# mdriver_8231A.net
KiCad netlist of a schematic drawn in EAGLE
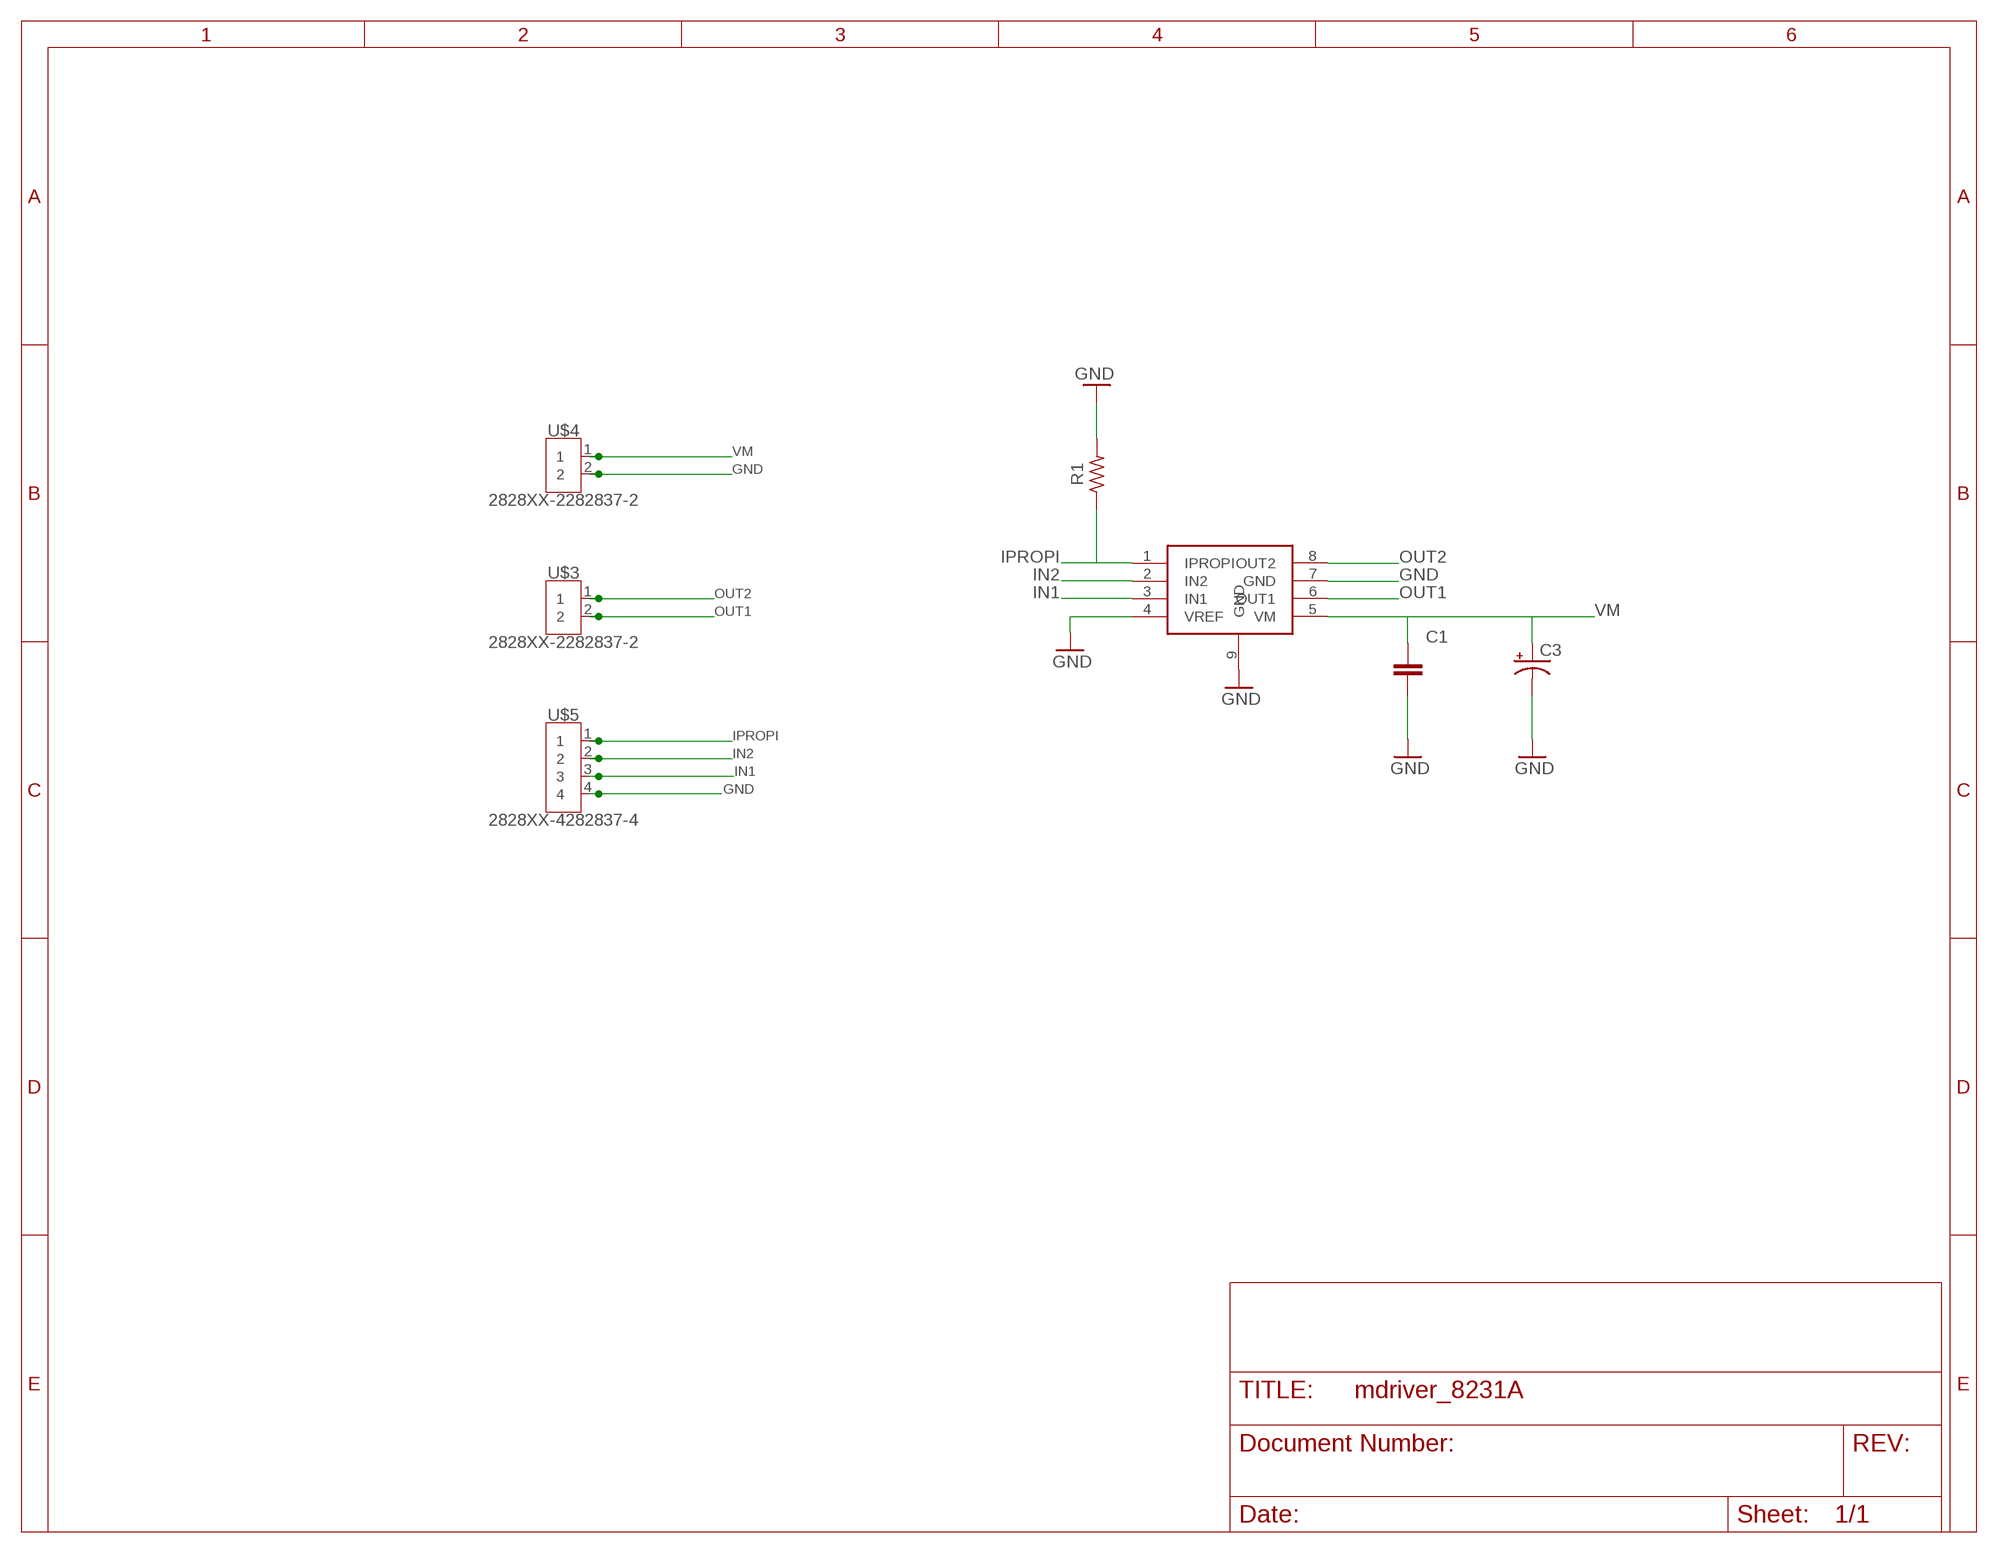
[diagram p0: schematic, sheet 1]

(export (version "E")
  (design (tool "Eeschema 10.0.6"))
  (components
    (comp (ref "C1")
      (value "C_CHIP-1206(3216-METRIC)")
      (footprint "eagle-import:CAPC3216X135")
      (libsource (lib "eagle-import") (part "CCHIP-1206(3216-METRIC)_"))
    )
    (comp (ref "C3")
      (value "C-POL-US_ECAP-10.5MM")
      (footprint "eagle-import:CAPAE1030X1050N")
      (libsource (lib "eagle-import") (part "C-POL-USECAP-10.5MM_"))
    )
    (comp (ref "R1")
      (value "R-US_CHIP-0603(1608-METRIC)")
      (footprint "eagle-import:RESC1608X60")
      (libsource (lib "eagle-import") (part "R-USCHIP-0603(1608-METRIC)_"))
    )
    (comp (ref "U$1")
      (value "DRV8231A")
      (footprint "eagle-import:SOIC127P580X170-9T271X340N")
      (libsource (lib "eagle-import") (part "DRV8231A"))
    )
    (comp (ref "U$3")
      (value "2828XX-2282837-2")
      (footprint "eagle-import:TERMBLK_508-2N")
      (fields (field (name "MANUFACTURER") "TE Connectivity") (field (name "MPN") "282837-2"))
      (libsource (lib "eagle-import") (part "2828XX-2282837-2"))
    )
    (comp (ref "U$4")
      (value "2828XX-2282837-2")
      (footprint "eagle-import:TERMBLK_508-2N")
      (fields (field (name "MANUFACTURER") "TE Connectivity") (field (name "MPN") "282837-2"))
      (libsource (lib "eagle-import") (part "2828XX-2282837-2"))
    )
    (comp (ref "U$5")
      (value "2828XX-4282837-4")
      (footprint "eagle-import:TERMBLK_508-4N")
      (fields (field (name "MANUFACTURER") "TE Connectivity") (field (name "MPN") "282837-4"))
      (libsource (lib "eagle-import") (part "2828XX-4282837-4"))
    )
  )
  (nets
    (net (code "1") (name "/IN1") (class "Default")
      (node (ref "U$1") (pin "3") (pinfunction "IN1_3") (pintype "bidirectional"))
      (node (ref "U$5") (pin "3") (pinfunction "3_3") (pintype "bidirectional"))
    )
    (net (code "2") (name "/IN2") (class "Default")
      (node (ref "U$1") (pin "2") (pinfunction "IN2_2") (pintype "bidirectional"))
      (node (ref "U$5") (pin "2") (pinfunction "2_2") (pintype "bidirectional"))
    )
    (net (code "3") (name "/IPROPI") (class "Default")
      (node (ref "R1") (pin "1") (pinfunction "1_1") (pintype "passive"))
      (node (ref "U$1") (pin "1") (pinfunction "IPROPI_1") (pintype "bidirectional"))
      (node (ref "U$5") (pin "1") (pinfunction "1_1") (pintype "bidirectional"))
    )
    (net (code "4") (name "/OUT1") (class "Default")
      (node (ref "U$1") (pin "6") (pinfunction "OUT1_6") (pintype "bidirectional"))
      (node (ref "U$3") (pin "2") (pinfunction "2_2") (pintype "bidirectional"))
    )
    (net (code "5") (name "/OUT2") (class "Default")
      (node (ref "U$1") (pin "8") (pinfunction "OUT2_8") (pintype "bidirectional"))
      (node (ref "U$3") (pin "1") (pinfunction "1_1") (pintype "bidirectional"))
    )
    (net (code "6") (name "/VM") (class "Default")
      (node (ref "C1") (pin "1") (pinfunction "1_1") (pintype "passive"))
      (node (ref "C3") (pin "1") (pinfunction "+_1") (pintype "passive"))
      (node (ref "U$1") (pin "5") (pinfunction "VM_5") (pintype "bidirectional"))
      (node (ref "U$4") (pin "1") (pinfunction "1_1") (pintype "bidirectional"))
    )
    (net (code "7") (name "GND") (class "Default")
      (node (ref "C1") (pin "2") (pinfunction "2_2") (pintype "passive"))
      (node (ref "C3") (pin "2") (pinfunction "-_2") (pintype "passive"))
      (node (ref "R1") (pin "2") (pinfunction "2_2") (pintype "passive"))
      (node (ref "U$1") (pin "4") (pinfunction "VREF_4") (pintype "bidirectional"))
      (node (ref "U$1") (pin "7") (pinfunction "GND_7") (pintype "bidirectional"))
      (node (ref "U$1") (pin "9") (pinfunction "GND_9") (pintype "bidirectional"))
      (node (ref "U$4") (pin "2") (pinfunction "2_2") (pintype "bidirectional"))
      (node (ref "U$5") (pin "4") (pinfunction "4_4") (pintype "bidirectional"))
    )
  )
)
